# Pulse_sensor.net
KiCad netlist of a schematic drawn in Altium Designer
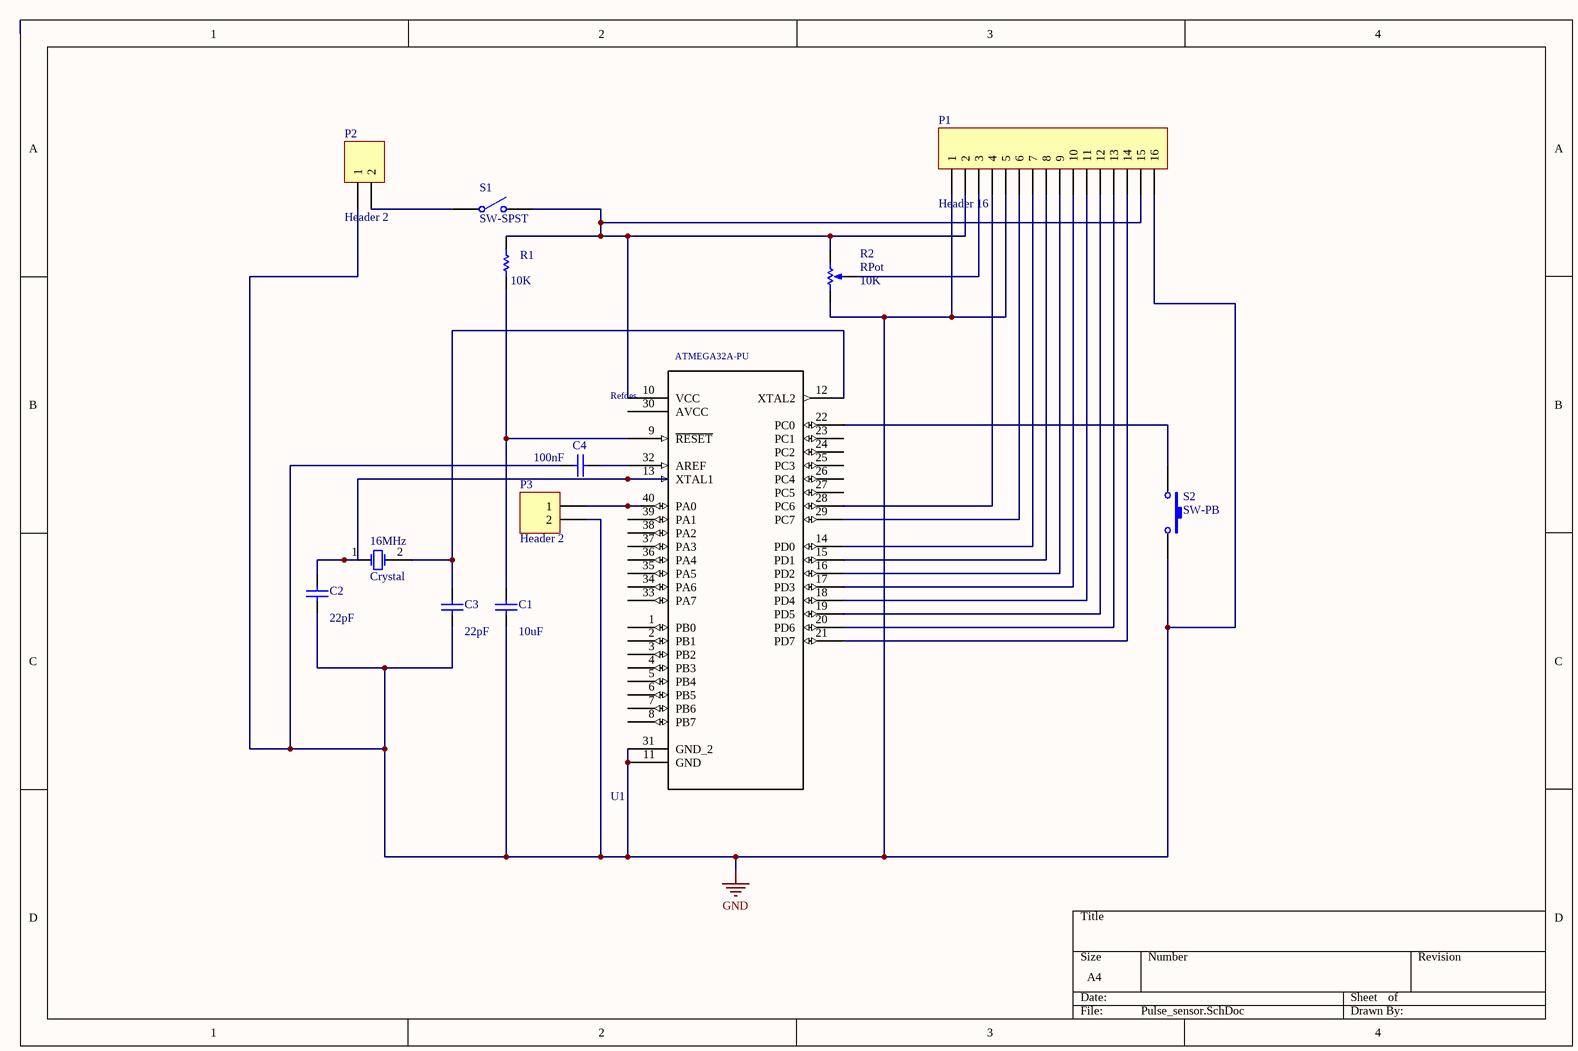
[diagram p0: Pulse_sensor.SchDoc]

(export (version "E")
  (design (tool "Eeschema 10.0.6"))
  (components
    (comp (ref "16MHz")
      (value "Crystal")
      (footprint "R38")
      (description "Crystal Oscillator")
      (fields (field (name "PUBLISHER") "Altium Limited"))
      (libsource (lib "Miscellaneous Devices") (part "XTAL"))
    )
    (comp (ref "C1")
      (value "10uF")
      (footprint "RAD-0.3")
      (description "Capacitor")
      (fields (field (name "Comment") "Cap") (field (name "PUBLISHER") "Altium Limited"))
      (libsource (lib "Miscellaneous Devices") (part "Cap"))
    )
    (comp (ref "C2")
      (value "22pF")
      (footprint "RAD-0.3")
      (description "Capacitor")
      (fields (field (name "Comment") "Cap") (field (name "PUBLISHER") "Altium Limited"))
      (libsource (lib "Miscellaneous Devices") (part "Cap"))
    )
    (comp (ref "C3")
      (value "22pF")
      (footprint "RAD-0.3")
      (description "Capacitor")
      (fields (field (name "Comment") "Cap") (field (name "PUBLISHER") "Altium Limited"))
      (libsource (lib "Miscellaneous Devices") (part "Cap"))
    )
    (comp (ref "C4")
      (value "100nF")
      (footprint "RAD-0.3")
      (description "Capacitor")
      (fields (field (name "Comment") "Cap") (field (name "PUBLISHER") "Altium Limited"))
      (libsource (lib "Miscellaneous Devices") (part "Cap"))
    )
    (comp (ref "P1")
      (value "Header 16")
      (footprint "HDR1X16")
      (description "Header, 16-Pin")
      (fields (field (name "PUBLISHER") "Altium Limited"))
      (libsource (lib "Miscellaneous Connectors") (part "Header 16"))
    )
    (comp (ref "P2")
      (value "Header 2")
      (footprint "HDR1X2")
      (description "Header, 2-Pin")
      (fields (field (name "PUBLISHER") "Altium Limited"))
      (libsource (lib "") (part "Header 2_1"))
    )
    (comp (ref "P3")
      (value "Header 2")
      (footprint "HDR1X2")
      (description "Header, 2-Pin")
      (fields (field (name "PUBLISHER") "Altium Limited"))
      (libsource (lib "Miscellaneous Connectors") (part "Header 2"))
    )
    (comp (ref "R1")
      (value "10K")
      (footprint "AXIAL-0.3")
      (description "Resistor")
      (fields (field (name "Comment") "Res1") (field (name "PUBLISHER") "Altium Limited"))
      (libsource (lib "Miscellaneous Devices") (part "Res1"))
    )
    (comp (ref "R2")
      (value "RPot")
      (footprint "VR5")
      (description "Potentiometer")
      (fields (field (name "ALTIUM_VALUE") "10K") (field (name "PUBLISHER") "Altium Limited"))
      (libsource (lib "Miscellaneous Devices") (part "RPot"))
    )
    (comp (ref "S1")
      (value "SW-SPST")
      (footprint "SPST-2")
      (description "Single-Pole, Single-Throw Switch")
      (fields (field (name "PUBLISHER") "Altium Limited"))
      (libsource (lib "Miscellaneous Devices") (part "SW-SPST"))
    )
    (comp (ref "S2")
      (value "SW-PB")
      (footprint "SPST-2")
      (description "Switch")
      (fields (field (name "PUBLISHER") "Altium Limited"))
      (libsource (lib "Miscellaneous Devices") (part "SW-PB"))
    )
    (comp (ref "U1")
      (value "ATMEGA32A-PU")
      (footprint "DIP254P1524X482-40")
      (description "ATmega Series 16 MHz 32 KB Flash 2 KB SRAM 8-Bit Microcontroller - DIP-40_Ã‘Ã’")
      (fields (field (name "MF") "Microchip"))
      (libsource (lib "ATMEGA32A-PU") (part "ATMEGA32A-PU"))
    )
  )
  (nets
    (net (code "1") (name "GND") (class "Default")
      (node (ref "C1") (pin "1") (pinfunction "1_1") (pintype "passive"))
      (node (ref "C2") (pin "1") (pinfunction "1_1") (pintype "passive"))
      (node (ref "C3") (pin "1") (pinfunction "1_1") (pintype "passive"))
      (node (ref "C4") (pin "1") (pinfunction "1_1") (pintype "passive"))
      (node (ref "P1") (pin "1") (pinfunction "1_1") (pintype "passive"))
      (node (ref "P1") (pin "16") (pinfunction "16_16") (pintype "passive"))
      (node (ref "P1") (pin "5") (pinfunction "5_5") (pintype "passive"))
      (node (ref "P2") (pin "1") (pinfunction "1_1") (pintype "passive"))
      (node (ref "P3") (pin "2") (pinfunction "2_2") (pintype "passive"))
      (node (ref "R2") (pin "1") (pinfunction "TOP_1") (pintype "passive"))
      (node (ref "S2") (pin "2") (pinfunction "2_2") (pintype "passive"))
      (node (ref "U1") (pin "11") (pinfunction "GND_11") (pintype "passive"))
      (node (ref "U1") (pin "31") (pinfunction "GND_2_31") (pintype "passive"))
    )
    (net (code "2") (name "Net-(16MHz-OSC1)") (class "Default")
      (node (ref "16MHz") (pin "1") (pinfunction "OSC1_1") (pintype "passive"))
      (node (ref "C2") (pin "2") (pinfunction "2_2") (pintype "passive"))
      (node (ref "U1") (pin "13") (pinfunction "XTAL1_13") (pintype "input"))
    )
    (net (code "3") (name "Net-(16MHz-OSC2)") (class "Default")
      (node (ref "16MHz") (pin "2") (pinfunction "OSC2_2") (pintype "passive"))
      (node (ref "C3") (pin "2") (pinfunction "2_2") (pintype "passive"))
      (node (ref "U1") (pin "12") (pinfunction "XTAL2_12") (pintype "output"))
    )
    (net (code "4") (name "Net-(R2-BOT)") (class "Default")
      (node (ref "P1") (pin "15") (pinfunction "15_15") (pintype "passive"))
      (node (ref "P1") (pin "2") (pinfunction "2_2") (pintype "passive"))
      (node (ref "R1") (pin "2") (pinfunction "2_2") (pintype "passive"))
      (node (ref "R2") (pin "2") (pinfunction "BOT_2") (pintype "passive"))
      (node (ref "S1") (pin "2") (pinfunction "NO_2") (pintype "passive"))
      (node (ref "U1") (pin "10") (pinfunction "VCC_10") (pintype "power_in"))
    )
    (net (code "5") (name "Net-(R2-TAP)") (class "Default")
      (node (ref "P1") (pin "3") (pinfunction "3_3") (pintype "passive"))
      (node (ref "R2") (pin "3") (pinfunction "TAP_3") (pintype "passive"))
    )
    (net (code "6") (name "Net-(S1-COMMON)") (class "Default")
      (node (ref "P2") (pin "2") (pinfunction "2_2") (pintype "passive"))
      (node (ref "S1") (pin "1") (pinfunction "COMMON_1") (pintype "passive"))
    )
    (net (code "7") (name "Net-(U1-AREF)") (class "Default")
      (node (ref "C4") (pin "2") (pinfunction "2_2") (pintype "passive"))
      (node (ref "U1") (pin "32") (pinfunction "AREF_32") (pintype "input"))
    )
    (net (code "8") (name "Net-(U1-PA0)") (class "Default")
      (node (ref "P3") (pin "1") (pinfunction "1_1") (pintype "passive"))
      (node (ref "U1") (pin "40") (pinfunction "PA0_40") (pintype "bidirectional"))
    )
    (net (code "9") (name "Net-(U1-PC0)") (class "Default")
      (node (ref "S2") (pin "1") (pinfunction "1_1") (pintype "passive"))
      (node (ref "U1") (pin "22") (pinfunction "PC0_22") (pintype "bidirectional"))
    )
    (net (code "10") (name "Net-(U1-PC6)") (class "Default")
      (node (ref "P1") (pin "4") (pinfunction "4_4") (pintype "passive"))
      (node (ref "U1") (pin "28") (pinfunction "PC6_28") (pintype "bidirectional"))
    )
    (net (code "11") (name "Net-(U1-PC7)") (class "Default")
      (node (ref "P1") (pin "6") (pinfunction "6_6") (pintype "passive"))
      (node (ref "U1") (pin "29") (pinfunction "PC7_29") (pintype "bidirectional"))
    )
    (net (code "12") (name "Net-(U1-PD0)") (class "Default")
      (node (ref "P1") (pin "7") (pinfunction "7_7") (pintype "passive"))
      (node (ref "U1") (pin "14") (pinfunction "PD0_14") (pintype "bidirectional"))
    )
    (net (code "13") (name "Net-(U1-PD1)") (class "Default")
      (node (ref "P1") (pin "8") (pinfunction "8_8") (pintype "passive"))
      (node (ref "U1") (pin "15") (pinfunction "PD1_15") (pintype "bidirectional"))
    )
    (net (code "14") (name "Net-(U1-PD2)") (class "Default")
      (node (ref "P1") (pin "9") (pinfunction "9_9") (pintype "passive"))
      (node (ref "U1") (pin "16") (pinfunction "PD2_16") (pintype "bidirectional"))
    )
    (net (code "15") (name "Net-(U1-PD3)") (class "Default")
      (node (ref "P1") (pin "10") (pinfunction "10_10") (pintype "passive"))
      (node (ref "U1") (pin "17") (pinfunction "PD3_17") (pintype "bidirectional"))
    )
    (net (code "16") (name "Net-(U1-PD4)") (class "Default")
      (node (ref "P1") (pin "11") (pinfunction "11_11") (pintype "passive"))
      (node (ref "U1") (pin "18") (pinfunction "PD4_18") (pintype "bidirectional"))
    )
    (net (code "17") (name "Net-(U1-PD5)") (class "Default")
      (node (ref "P1") (pin "12") (pinfunction "12_12") (pintype "passive"))
      (node (ref "U1") (pin "19") (pinfunction "PD5_19") (pintype "bidirectional"))
    )
    (net (code "18") (name "Net-(U1-PD6)") (class "Default")
      (node (ref "P1") (pin "13") (pinfunction "13_13") (pintype "passive"))
      (node (ref "U1") (pin "20") (pinfunction "PD6_20") (pintype "bidirectional"))
    )
    (net (code "19") (name "Net-(U1-PD7)") (class "Default")
      (node (ref "P1") (pin "14") (pinfunction "14_14") (pintype "passive"))
      (node (ref "U1") (pin "21") (pinfunction "PD7_21") (pintype "bidirectional"))
    )
    (net (code "20") (name "Net-(U1-~{RESET})") (class "Default")
      (node (ref "C1") (pin "2") (pinfunction "2_2") (pintype "passive"))
      (node (ref "R1") (pin "1") (pinfunction "1_1") (pintype "passive"))
      (node (ref "U1") (pin "9") (pinfunction "~{RESET}_9") (pintype "input"))
    )
    (net (code "21") (name "unconnected-(U1-AVCC-Pad30)") (class "Default")
      (node (ref "U1") (pin "30") (pinfunction "AVCC_30") (pintype "power_in"))
    )
    (net (code "22") (name "unconnected-(U1-PA1-Pad39)") (class "Default")
      (node (ref "U1") (pin "39") (pinfunction "PA1_39") (pintype "bidirectional"))
    )
    (net (code "23") (name "unconnected-(U1-PA2-Pad38)") (class "Default")
      (node (ref "U1") (pin "38") (pinfunction "PA2_38") (pintype "bidirectional"))
    )
    (net (code "24") (name "unconnected-(U1-PA3-Pad37)") (class "Default")
      (node (ref "U1") (pin "37") (pinfunction "PA3_37") (pintype "bidirectional"))
    )
    (net (code "25") (name "unconnected-(U1-PA4-Pad36)") (class "Default")
      (node (ref "U1") (pin "36") (pinfunction "PA4_36") (pintype "bidirectional"))
    )
    (net (code "26") (name "unconnected-(U1-PA5-Pad35)") (class "Default")
      (node (ref "U1") (pin "35") (pinfunction "PA5_35") (pintype "bidirectional"))
    )
    (net (code "27") (name "unconnected-(U1-PA6-Pad34)") (class "Default")
      (node (ref "U1") (pin "34") (pinfunction "PA6_34") (pintype "bidirectional"))
    )
    (net (code "28") (name "unconnected-(U1-PA7-Pad33)") (class "Default")
      (node (ref "U1") (pin "33") (pinfunction "PA7_33") (pintype "bidirectional"))
    )
    (net (code "29") (name "unconnected-(U1-PB0-Pad1)") (class "Default")
      (node (ref "U1") (pin "1") (pinfunction "PB0_1") (pintype "bidirectional"))
    )
    (net (code "30") (name "unconnected-(U1-PB1-Pad2)") (class "Default")
      (node (ref "U1") (pin "2") (pinfunction "PB1_2") (pintype "bidirectional"))
    )
    (net (code "31") (name "unconnected-(U1-PB2-Pad3)") (class "Default")
      (node (ref "U1") (pin "3") (pinfunction "PB2_3") (pintype "bidirectional"))
    )
    (net (code "32") (name "unconnected-(U1-PB3-Pad4)") (class "Default")
      (node (ref "U1") (pin "4") (pinfunction "PB3_4") (pintype "bidirectional"))
    )
    (net (code "33") (name "unconnected-(U1-PB4-Pad5)") (class "Default")
      (node (ref "U1") (pin "5") (pinfunction "PB4_5") (pintype "bidirectional"))
    )
    (net (code "34") (name "unconnected-(U1-PB5-Pad6)") (class "Default")
      (node (ref "U1") (pin "6") (pinfunction "PB5_6") (pintype "bidirectional"))
    )
    (net (code "35") (name "unconnected-(U1-PB6-Pad7)") (class "Default")
      (node (ref "U1") (pin "7") (pinfunction "PB6_7") (pintype "bidirectional"))
    )
    (net (code "36") (name "unconnected-(U1-PB7-Pad8)") (class "Default")
      (node (ref "U1") (pin "8") (pinfunction "PB7_8") (pintype "bidirectional"))
    )
    (net (code "37") (name "unconnected-(U1-PC1-Pad23)") (class "Default")
      (node (ref "U1") (pin "23") (pinfunction "PC1_23") (pintype "bidirectional"))
    )
    (net (code "38") (name "unconnected-(U1-PC2-Pad24)") (class "Default")
      (node (ref "U1") (pin "24") (pinfunction "PC2_24") (pintype "bidirectional"))
    )
    (net (code "39") (name "unconnected-(U1-PC3-Pad25)") (class "Default")
      (node (ref "U1") (pin "25") (pinfunction "PC3_25") (pintype "bidirectional"))
    )
    (net (code "40") (name "unconnected-(U1-PC4-Pad26)") (class "Default")
      (node (ref "U1") (pin "26") (pinfunction "PC4_26") (pintype "bidirectional"))
    )
    (net (code "41") (name "unconnected-(U1-PC5-Pad27)") (class "Default")
      (node (ref "U1") (pin "27") (pinfunction "PC5_27") (pintype "bidirectional"))
    )
  )
)
